# PSU.net
KiCad netlist of a schematic drawn in Altium Designer
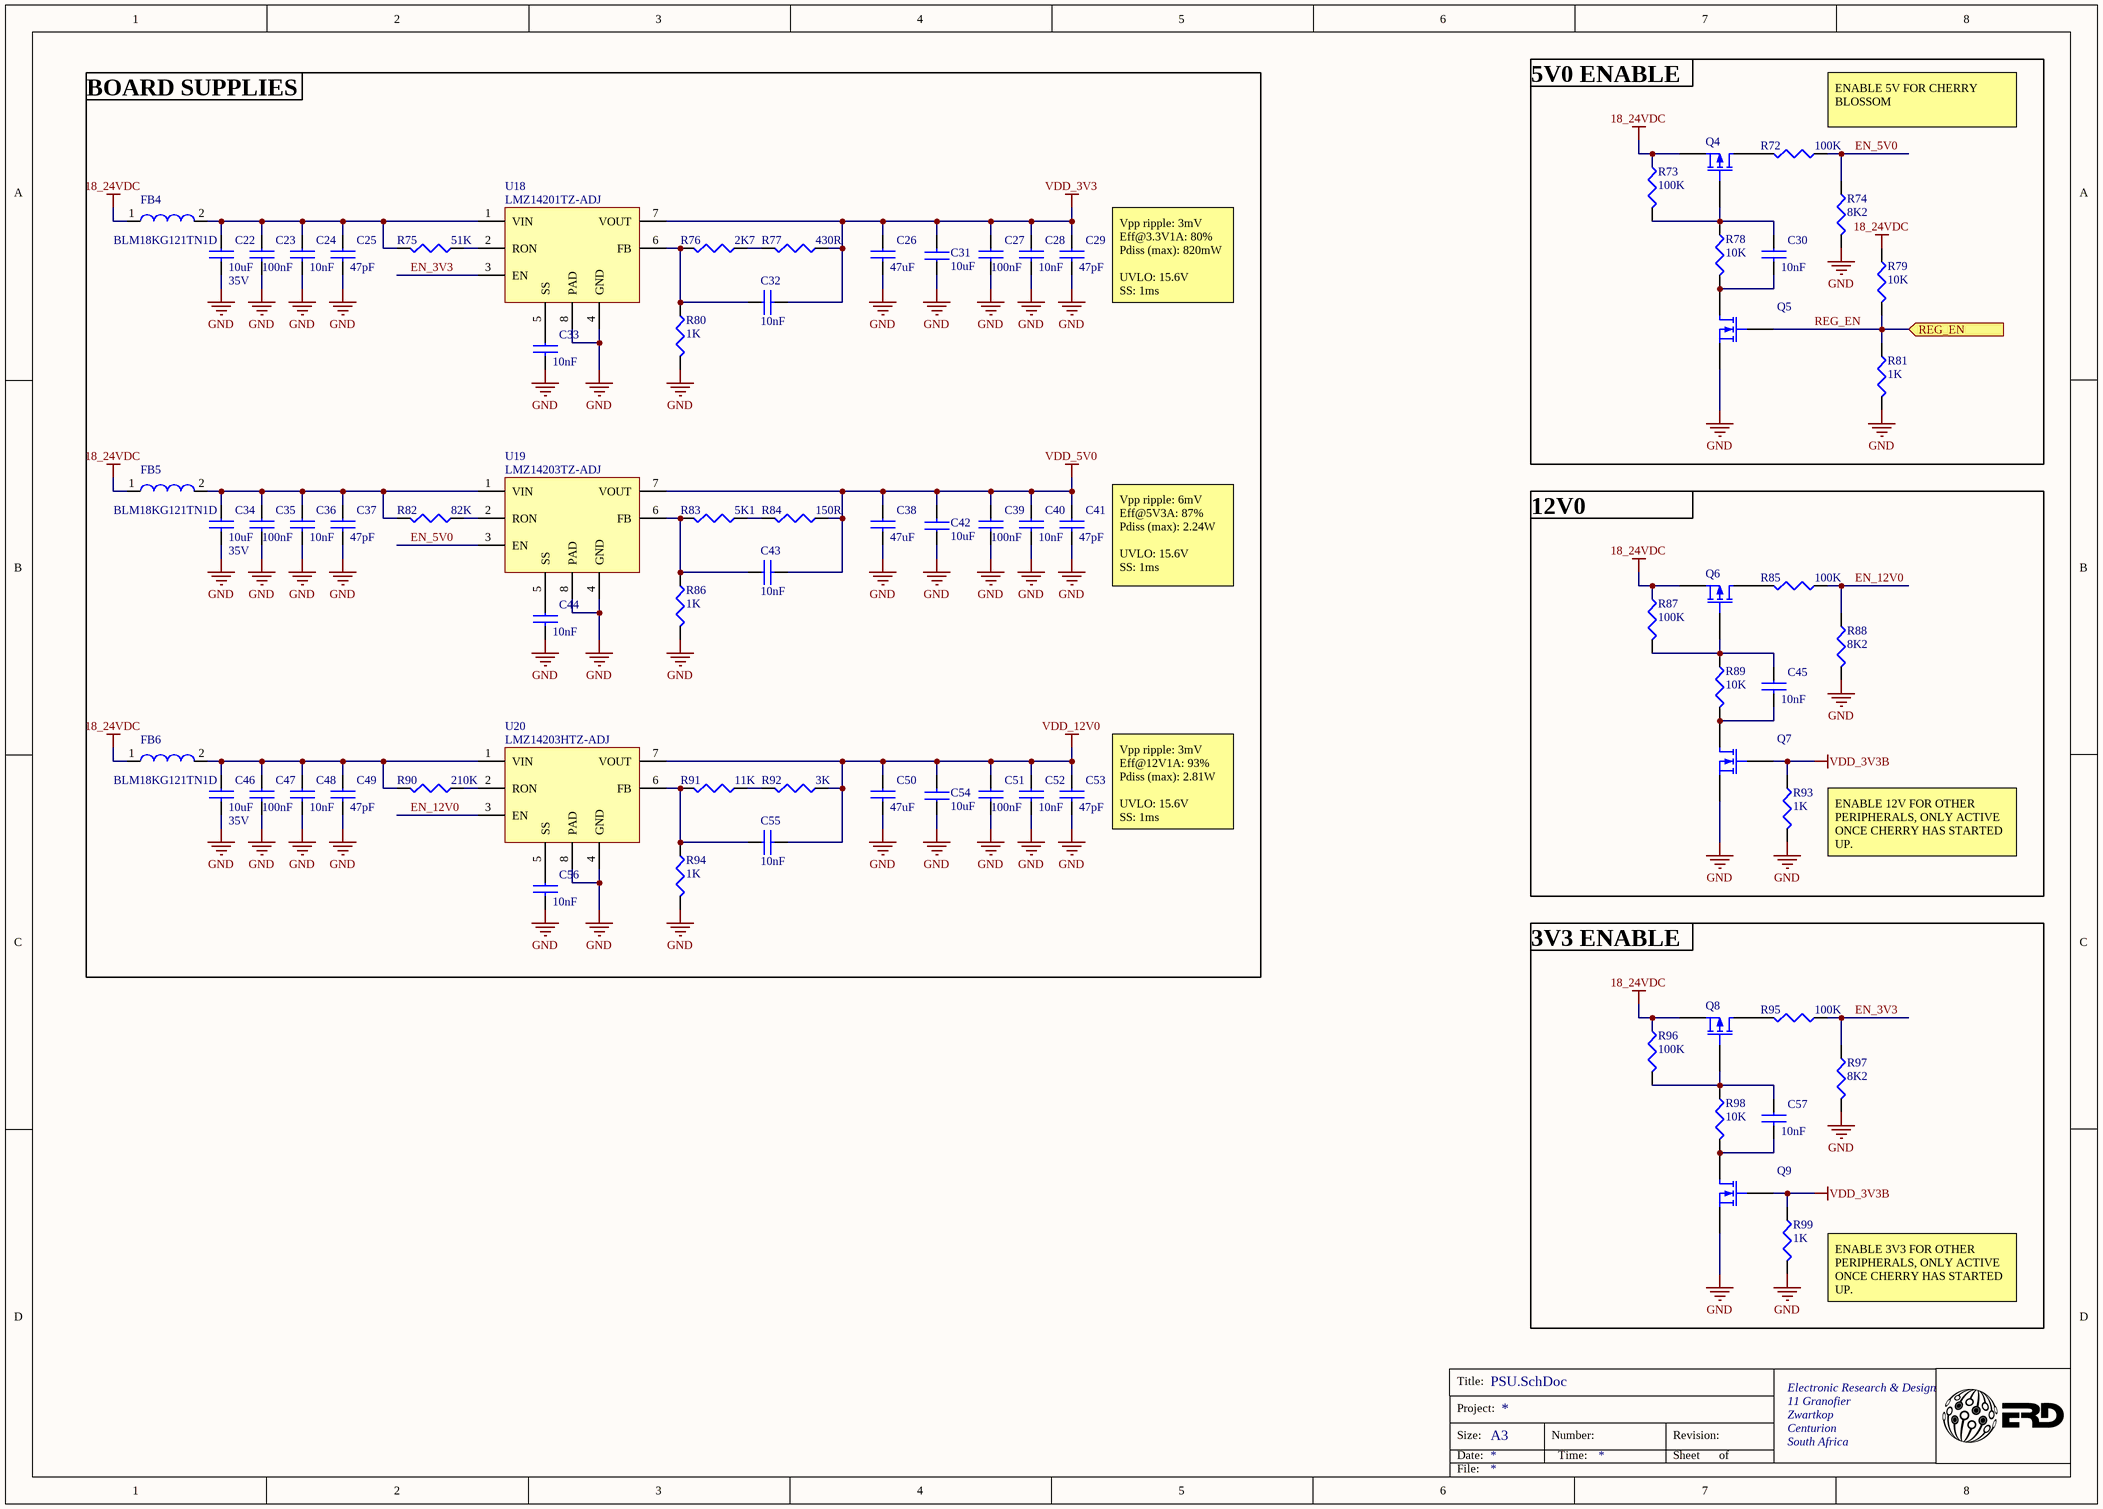
[diagram p0: PSU.SchDoc]

(export (version "E")
  (design (tool "Eeschema 10.0.6"))
  (components
    (comp (ref "C22")
      (value "10uF")
      (footprint "CC0805")
      (description "CAP CER 10UF 35V 10% X5R 0805")
      (fields
        (field (name "MANUFACTURER") "Murata")
        (field (name "PART NUMBER") "GRM21BR6YA106KE43L")
        (field (name "VOLTAGE RATING") "35V")
      )
      (libsource (lib "ERD TiAm") (part "CAP CER 0.1UF 10V 10% X5R 0402"))
    )
    (comp (ref "C23")
      (value "100nF")
      (footprint "CC0402")
      (description "CAP CER 0.1UF 50V 10% X7R 0402")
      (fields (field (name "MANUFACTURER") "Murata") (field (name "PART NUMBER") "GCM155R71H104KE02D"))
      (libsource (lib "ERD TiAm") (part "CAP CER 0.1UF 10V 10% X5R 0402"))
    )
    (comp (ref "C24")
      (value "10nF")
      (footprint "CC0402")
      (description "CAP CER 10NF 50V 10% X7R 0402")
      (fields (field (name "MANUFACTURER") "Murata") (field (name "PART NUMBER") "GRM155R71H103KA88J"))
      (libsource (lib "ERD TiAm") (part "CAP CER 0.1UF 10V 10% X5R 0402"))
    )
    (comp (ref "C25")
      (value "47pF")
      (footprint "CC0402")
      (description "CAP CER 47PF 50V 5% C0G/NP0 0402")
      (fields (field (name "MANUFACTURER") "Murata") (field (name "PART NUMBER") "GCM1555C1H470JA16D"))
      (libsource (lib "ERD TiAm") (part "CAP CER 0.1UF 10V 10% X5R 0402"))
    )
    (comp (ref "C26")
      (value "47uF")
      (footprint "RC1206")
      (description "CAP CER 47UF 25V 20% X5R 1206")
      (fields (field (name "MANUFACTURER") "Murata") (field (name "PART NUMBER") "C3216X5R1E476M160AC"))
      (libsource (lib "ERD TiAm") (part "CAP CER 0.1UF 10V 10% X5R 0402"))
    )
    (comp (ref "C27")
      (value "100nF")
      (footprint "CC0402")
      (description "CAP CER 0.1UF 50V 10% X7R 0402")
      (fields (field (name "MANUFACTURER") "Murata") (field (name "PART NUMBER") "GCM155R71H104KE02D"))
      (libsource (lib "ERD TiAm") (part "CAP CER 0.1UF 10V 10% X5R 0402"))
    )
    (comp (ref "C28")
      (value "10nF")
      (footprint "CC0402")
      (description "CAP CER 10NF 50V 10% X7R 0402")
      (fields (field (name "MANUFACTURER") "Murata") (field (name "PART NUMBER") "GRM155R71H103KA88J"))
      (libsource (lib "ERD TiAm") (part "CAP CER 0.1UF 10V 10% X5R 0402"))
    )
    (comp (ref "C29")
      (value "47pF")
      (footprint "CC0402")
      (description "CAP CER 47PF 50V 5% C0G/NP0 0402")
      (fields (field (name "MANUFACTURER") "Murata") (field (name "PART NUMBER") "GCM1555C1H470JA16D"))
      (libsource (lib "ERD TiAm") (part "CAP CER 0.1UF 10V 10% X5R 0402"))
    )
    (comp (ref "C30")
      (value "10nF")
      (footprint "CC0402")
      (description "CAP CER 10NF 50V 10% X7R 0402")
      (fields (field (name "MANUFACTURER") "Murata") (field (name "PART NUMBER") "GRM155R71H103KA88J"))
      (libsource (lib "ERD TiAm") (part "CAP CER 0.1UF 10V 10% X5R 0402"))
    )
    (comp (ref "C31")
      (value "10uF")
      (footprint "CC0603")
      (description "CAP CER 10UF 25V 20% X5R 0603")
      (fields (field (name "MANUFACTURER") "Murata") (field (name "PARTNUMBER") "GRM188R61E106MA73D"))
      (libsource (lib "ERD TiAm") (part "CAP CER 0.1UF 10V 10% X5R 0402"))
    )
    (comp (ref "C32")
      (value "10nF")
      (footprint "CC0402")
      (description "CAP CER 10NF 50V 10% X7R 0402")
      (fields (field (name "MANUFACTURER") "Murata") (field (name "PART NUMBER") "GRM155R71H103KA88J"))
      (libsource (lib "ERD TiAm") (part "CAP CER 0.1UF 10V 10% X5R 0402"))
    )
    (comp (ref "C33")
      (value "10nF")
      (footprint "CC0402")
      (description "CAP CER 10NF 50V 10% X7R 0402")
      (fields (field (name "MANUFACTURER") "Murata") (field (name "PART NUMBER") "GRM155R71H103KA88J"))
      (libsource (lib "ERD TiAm") (part "CAP CER 0.1UF 10V 10% X5R 0402"))
    )
    (comp (ref "C34")
      (value "10uF")
      (footprint "CC0805")
      (description "CAP CER 10UF 35V 10% X5R 0805")
      (fields
        (field (name "MANUFACTURER") "Murata")
        (field (name "PART NUMBER") "GRM21BR6YA106KE43L")
        (field (name "VOLTAGE RATING") "35V")
      )
      (libsource (lib "ERD TiAm") (part "CAP CER 0.1UF 10V 10% X5R 0402"))
    )
    (comp (ref "C35")
      (value "100nF")
      (footprint "CC0402")
      (description "CAP CER 0.1UF 50V 10% X7R 0402")
      (fields (field (name "MANUFACTURER") "Murata") (field (name "PART NUMBER") "GCM155R71H104KE02D"))
      (libsource (lib "ERD TiAm") (part "CAP CER 0.1UF 10V 10% X5R 0402"))
    )
    (comp (ref "C36")
      (value "10nF")
      (footprint "CC0402")
      (description "CAP CER 10NF 50V 10% X7R 0402")
      (fields (field (name "MANUFACTURER") "Murata") (field (name "PART NUMBER") "GRM155R71H103KA88J"))
      (libsource (lib "ERD TiAm") (part "CAP CER 0.1UF 10V 10% X5R 0402"))
    )
    (comp (ref "C37")
      (value "47pF")
      (footprint "CC0402")
      (description "CAP CER 47PF 50V 5% C0G/NP0 0402")
      (fields (field (name "MANUFACTURER") "Murata") (field (name "PART NUMBER") "GCM1555C1H470JA16D"))
      (libsource (lib "ERD TiAm") (part "CAP CER 0.1UF 10V 10% X5R 0402"))
    )
    (comp (ref "C38")
      (value "47uF")
      (footprint "RC1206")
      (description "CAP CER 47UF 25V 20% X5R 1206")
      (fields (field (name "MANUFACTURER") "Murata") (field (name "PART NUMBER") "C3216X5R1E476M160AC"))
      (libsource (lib "ERD TiAm") (part "CAP CER 0.1UF 10V 10% X5R 0402"))
    )
    (comp (ref "C39")
      (value "100nF")
      (footprint "CC0402")
      (description "CAP CER 0.1UF 50V 10% X7R 0402")
      (fields (field (name "MANUFACTURER") "Murata") (field (name "PART NUMBER") "GCM155R71H104KE02D"))
      (libsource (lib "ERD TiAm") (part "CAP CER 0.1UF 10V 10% X5R 0402"))
    )
    (comp (ref "C40")
      (value "10nF")
      (footprint "CC0402")
      (description "CAP CER 10NF 50V 10% X7R 0402")
      (fields (field (name "MANUFACTURER") "Murata") (field (name "PART NUMBER") "GRM155R71H103KA88J"))
      (libsource (lib "ERD TiAm") (part "CAP CER 0.1UF 10V 10% X5R 0402"))
    )
    (comp (ref "C41")
      (value "47pF")
      (footprint "CC0402")
      (description "CAP CER 47PF 50V 5% C0G/NP0 0402")
      (fields (field (name "MANUFACTURER") "Murata") (field (name "PART NUMBER") "GCM1555C1H470JA16D"))
      (libsource (lib "ERD TiAm") (part "CAP CER 0.1UF 10V 10% X5R 0402"))
    )
    (comp (ref "C42")
      (value "10uF")
      (footprint "CC0603")
      (description "CAP CER 10UF 25V 20% X5R 0603")
      (fields (field (name "MANUFACTURER") "Murata") (field (name "PARTNUMBER") "GRM188R61E106MA73D"))
      (libsource (lib "ERD TiAm") (part "CAP CER 0.1UF 10V 10% X5R 0402"))
    )
    (comp (ref "C43")
      (value "10nF")
      (footprint "CC0402")
      (description "CAP CER 10NF 50V 10% X7R 0402")
      (fields (field (name "MANUFACTURER") "Murata") (field (name "PART NUMBER") "GRM155R71H103KA88J"))
      (libsource (lib "ERD TiAm") (part "CAP CER 0.1UF 10V 10% X5R 0402"))
    )
    (comp (ref "C44")
      (value "10nF")
      (footprint "CC0402")
      (description "CAP CER 10NF 50V 10% X7R 0402")
      (fields (field (name "MANUFACTURER") "Murata") (field (name "PART NUMBER") "GRM155R71H103KA88J"))
      (libsource (lib "ERD TiAm") (part "CAP CER 0.1UF 10V 10% X5R 0402"))
    )
    (comp (ref "C45")
      (value "10nF")
      (footprint "CC0402")
      (description "CAP CER 10NF 50V 10% X7R 0402")
      (fields (field (name "MANUFACTURER") "Murata") (field (name "PART NUMBER") "GRM155R71H103KA88J"))
      (libsource (lib "ERD TiAm") (part "CAP CER 0.1UF 10V 10% X5R 0402"))
    )
    (comp (ref "C46")
      (value "10uF")
      (footprint "CC0805")
      (description "CAP CER 10UF 35V 10% X5R 0805")
      (fields
        (field (name "MANUFACTURER") "Murata")
        (field (name "PART NUMBER") "GRM21BR6YA106KE43L")
        (field (name "VOLTAGE RATING") "35V")
      )
      (libsource (lib "ERD TiAm") (part "CAP CER 0.1UF 10V 10% X5R 0402"))
    )
    (comp (ref "C47")
      (value "100nF")
      (footprint "CC0402")
      (description "CAP CER 0.1UF 50V 10% X7R 0402")
      (fields (field (name "MANUFACTURER") "Murata") (field (name "PART NUMBER") "GCM155R71H104KE02D"))
      (libsource (lib "ERD TiAm") (part "CAP CER 0.1UF 10V 10% X5R 0402"))
    )
    (comp (ref "C48")
      (value "10nF")
      (footprint "CC0402")
      (description "CAP CER 10NF 50V 10% X7R 0402")
      (fields (field (name "MANUFACTURER") "Murata") (field (name "PART NUMBER") "GRM155R71H103KA88J"))
      (libsource (lib "ERD TiAm") (part "CAP CER 0.1UF 10V 10% X5R 0402"))
    )
    (comp (ref "C49")
      (value "47pF")
      (footprint "CC0402")
      (description "CAP CER 47PF 50V 5% C0G/NP0 0402")
      (fields (field (name "MANUFACTURER") "Murata") (field (name "PART NUMBER") "GCM1555C1H470JA16D"))
      (libsource (lib "ERD TiAm") (part "CAP CER 0.1UF 10V 10% X5R 0402"))
    )
    (comp (ref "C50")
      (value "47uF")
      (footprint "RC1206")
      (description "CAP CER 47UF 25V 20% X5R 1206")
      (fields (field (name "MANUFACTURER") "Murata") (field (name "PART NUMBER") "C3216X5R1E476M160AC"))
      (libsource (lib "ERD TiAm") (part "CAP CER 0.1UF 10V 10% X5R 0402"))
    )
    (comp (ref "C51")
      (value "100nF")
      (footprint "CC0402")
      (description "CAP CER 0.1UF 50V 10% X7R 0402")
      (fields (field (name "MANUFACTURER") "Murata") (field (name "PART NUMBER") "GCM155R71H104KE02D"))
      (libsource (lib "ERD TiAm") (part "CAP CER 0.1UF 10V 10% X5R 0402"))
    )
    (comp (ref "C52")
      (value "10nF")
      (footprint "CC0402")
      (description "CAP CER 10NF 50V 10% X7R 0402")
      (fields (field (name "MANUFACTURER") "Murata") (field (name "PART NUMBER") "GRM155R71H103KA88J"))
      (libsource (lib "ERD TiAm") (part "CAP CER 0.1UF 10V 10% X5R 0402"))
    )
    (comp (ref "C53")
      (value "47pF")
      (footprint "CC0402")
      (description "CAP CER 47PF 50V 5% C0G/NP0 0402")
      (fields (field (name "MANUFACTURER") "Murata") (field (name "PART NUMBER") "GCM1555C1H470JA16D"))
      (libsource (lib "ERD TiAm") (part "CAP CER 0.1UF 10V 10% X5R 0402"))
    )
    (comp (ref "C54")
      (value "10uF")
      (footprint "CC0603")
      (description "CAP CER 10UF 25V 20% X5R 0603")
      (fields (field (name "MANUFACTURER") "Murata") (field (name "PARTNUMBER") "GRM188R61E106MA73D"))
      (libsource (lib "ERD TiAm") (part "CAP CER 0.1UF 10V 10% X5R 0402"))
    )
    (comp (ref "C55")
      (value "10nF")
      (footprint "CC0402")
      (description "CAP CER 10NF 50V 10% X7R 0402")
      (fields (field (name "MANUFACTURER") "Murata") (field (name "PART NUMBER") "GRM155R71H103KA88J"))
      (libsource (lib "ERD TiAm") (part "CAP CER 0.1UF 10V 10% X5R 0402"))
    )
    (comp (ref "C56")
      (value "10nF")
      (footprint "CC0402")
      (description "CAP CER 10NF 50V 10% X7R 0402")
      (fields (field (name "MANUFACTURER") "Murata") (field (name "PART NUMBER") "GRM155R71H103KA88J"))
      (libsource (lib "ERD TiAm") (part "CAP CER 0.1UF 10V 10% X5R 0402"))
    )
    (comp (ref "C57")
      (value "10nF")
      (footprint "CC0402")
      (description "CAP CER 10NF 50V 10% X7R 0402")
      (fields (field (name "MANUFACTURER") "Murata") (field (name "PART NUMBER") "GRM155R71H103KA88J"))
      (libsource (lib "ERD TiAm") (part "CAP CER 0.1UF 10V 10% X5R 0402"))
    )
    (comp (ref "FB4")
      (value "BLM18KG121TN1D")
      (footprint "LC0603")
      (description "FERRITE 3A 30mOHM 0603 SMD")
      (libsource (lib "BEAGLEBONEBLACK_REV A5B") (part "FER_180_200_0"))
    )
    (comp (ref "FB5")
      (value "BLM18KG121TN1D")
      (footprint "LC0603")
      (description "FERRITE 3A 30mOHM 0603 SMD")
      (libsource (lib "BEAGLEBONEBLACK_REV A5B") (part "FER_180_200_0"))
    )
    (comp (ref "FB6")
      (value "BLM18KG121TN1D")
      (footprint "LC0603")
      (description "FERRITE 3A 30mOHM 0603 SMD")
      (libsource (lib "BEAGLEBONEBLACK_REV A5B") (part "FER_180_200_0"))
    )
    (comp (ref "Q4")
      (value "MOSFET-P")
      (footprint "E3")
      (description "P-Channel MOSFET")
      (fields (field (name "PUBLISHER") "Altium Limited"))
      (libsource (lib "Miscellaneous Devices") (part "MOSFET-P"))
    )
    (comp (ref "Q5")
      (value "BSS214NWH6327XTSA1")
      (footprint "ERD TiAm:SOT323")
      (description "N-Channel FET, 20V, 1.5A, 140mOhm, SOT323")
      (fields (field (name "PUBLISHER") "Altium Limited"))
      (libsource (lib "Miscellaneous Devices") (part "MOSFET-N"))
    )
    (comp (ref "Q6")
      (value "MOSFET-P")
      (footprint "E3")
      (description "P-Channel MOSFET")
      (fields (field (name "PUBLISHER") "Altium Limited"))
      (libsource (lib "Miscellaneous Devices") (part "MOSFET-P"))
    )
    (comp (ref "Q7")
      (value "BSS214NWH6327XTSA1")
      (footprint "ERD TiAm:SOT323")
      (description "N-Channel FET, 20V, 1.5A, 140mOhm, SOT323")
      (fields (field (name "PUBLISHER") "Altium Limited"))
      (libsource (lib "Miscellaneous Devices") (part "MOSFET-N"))
    )
    (comp (ref "Q8")
      (value "MOSFET-P")
      (footprint "E3")
      (description "P-Channel MOSFET")
      (fields (field (name "PUBLISHER") "Altium Limited"))
      (libsource (lib "Miscellaneous Devices") (part "MOSFET-P"))
    )
    (comp (ref "Q9")
      (value "BSS214NWH6327XTSA1")
      (footprint "ERD TiAm:SOT323")
      (description "N-Channel FET, 20V, 1.5A, 140mOhm, SOT323")
      (fields (field (name "PUBLISHER") "Altium Limited"))
      (libsource (lib "Miscellaneous Devices") (part "MOSFET-N"))
    )
    (comp (ref "R72")
      (value "100K")
      (footprint "RC0402")
      (description "RES, 100K OHM, 1/16W, 1%, 0402")
      (fields (field (name "MANUFACTURER") "Yageo") (field (name "PARTNUMBER") "RC0402FR-07100KL"))
      (libsource (lib "ERD TiAm") (part "RES_10K_1/16W_1%_0402"))
    )
    (comp (ref "R73")
      (value "100K")
      (footprint "RC0402")
      (description "RES, 100K OHM, 1/16W, 1%, 0402")
      (fields (field (name "MANUFACTURER") "Yageo") (field (name "PART NUMBER") "RC0402FR-07100KL"))
      (libsource (lib "ERD TiAm") (part "RES_10K_1/16W_1%_0402"))
    )
    (comp (ref "R74")
      (value "8K2")
      (footprint "RC0402")
      (description "RES, 8K2 OHM, 1/16W, 1%, 0402")
      (fields (field (name "MANUFACTURER") "Yageo") (field (name "PARTNUMBER") "RC0402FR-078K2L"))
      (libsource (lib "ERD TiAm") (part "RES_10K_1/16W_1%_0402"))
    )
    (comp (ref "R75")
      (value "51K")
      (footprint "RC0402")
      (description "RES, 51K OHM, 1/16W, 1%, 0402")
      (fields (field (name "MANUFACTURER") "Yageo") (field (name "PARTNUMBER") "RC0402FR-0751KL"))
      (libsource (lib "ERD TiAm") (part "RES_10K_1/16W_1%_0402"))
    )
    (comp (ref "R76")
      (value "2K7")
      (footprint "RC0402")
      (description "RES, 2K7 OHM, 1/16W, 1%, 0402")
      (fields (field (name "MANUFACTURER") "Yageo") (field (name "PARTNUMBER") "RC0402FR-072K7L"))
      (libsource (lib "ERD TiAm") (part "RES_10K_1/16W_1%_0402"))
    )
    (comp (ref "R77")
      (value "430R")
      (footprint "RC0402")
      (description "RES, 430 OHM, 1/16W, 1%, 0402")
      (fields (field (name "MANUFACTURER") "Yageo") (field (name "PARTNUMBER") "RC0402FR-07430RL"))
      (libsource (lib "ERD TiAm") (part "RES_10K_1/16W_1%_0402"))
    )
    (comp (ref "R78")
      (value "10K")
      (footprint "RC0402")
      (description "RES, 10K OHM, 1/16W, 1%, 0402")
      (fields (field (name "MANUFACTURER") "Yageo") (field (name "PART NUMBER") "RC0402FR-0710KL"))
      (libsource (lib "ERD TiAm") (part "RES_10K_1/16W_1%_0402"))
    )
    (comp (ref "R79")
      (value "10K")
      (footprint "RC0402")
      (description "RES, 10K OHM, 1/16W, 1%, 0402")
      (fields (field (name "MANUFACTURER") "Yageo") (field (name "PART NUMBER") "RC0402FR-0710KL"))
      (libsource (lib "ERD TiAm") (part "RES_10K_1/16W_1%_0402"))
    )
    (comp (ref "R80")
      (value "1K")
      (footprint "RC0402")
      (description "RES, 1K OHM, 1/16W, 1%, 0402")
      (fields (field (name "MANUFACTURER") "Yageo") (field (name "PARTNUMBER") "RC0402FR-071KL"))
      (libsource (lib "ERD TiAm") (part "RES_10K_1/16W_1%_0402"))
    )
    (comp (ref "R81")
      (value "1K")
      (footprint "RC0402")
      (description "RES, 1K OHM, 1/16W, 1%, 0402")
      (fields (field (name "MANUFACTURER") "Yageo") (field (name "PARTNUMBER") "RC0402FR-071KL"))
      (libsource (lib "ERD TiAm") (part "RES_10K_1/16W_1%_0402"))
    )
    (comp (ref "R82")
      (value "82K")
      (footprint "RC0402")
      (description "RES, 82K OHM, 1/16W, 1%, 0402")
      (fields (field (name "MANUFACTURER") "Yageo") (field (name "PARTNUMBER") "RC0402FR-0782KL"))
      (libsource (lib "ERD TiAm") (part "RES_10K_1/16W_1%_0402"))
    )
    (comp (ref "R83")
      (value "5K1")
      (footprint "RC0402")
      (description "RES, 5K1 OHM, 1/16W, 1%, 0402")
      (fields (field (name "MANUFACTURER") "Yageo") (field (name "PARTNUMBER") "RC0402FR-075K1L"))
      (libsource (lib "ERD TiAm") (part "RES_10K_1/16W_1%_0402"))
    )
    (comp (ref "R84")
      (value "150R")
      (footprint "RC0402")
      (description "RES, 150 OHM, 1/16W, 1%, 0402")
      (fields (field (name "MANUFACTURER") "Yageo") (field (name "PARTNUMBER") "RC0402FR-07150RL"))
      (libsource (lib "ERD TiAm") (part "RES_10K_1/16W_1%_0402"))
    )
    (comp (ref "R85")
      (value "100K")
      (footprint "RC0402")
      (description "RES, 100K OHM, 1/16W, 1%, 0402")
      (fields (field (name "MANUFACTURER") "Yageo") (field (name "PARTNUMBER") "RC0402FR-07100KL"))
      (libsource (lib "ERD TiAm") (part "RES_10K_1/16W_1%_0402"))
    )
    (comp (ref "R86")
      (value "1K")
      (footprint "RC0402")
      (description "RES, 1K OHM, 1/16W, 1%, 0402")
      (fields (field (name "MANUFACTURER") "Yageo") (field (name "PARTNUMBER") "RC0402FR-071KL"))
      (libsource (lib "ERD TiAm") (part "RES_10K_1/16W_1%_0402"))
    )
    (comp (ref "R87")
      (value "100K")
      (footprint "RC0402")
      (description "RES, 100K OHM, 1/16W, 1%, 0402")
      (fields (field (name "MANUFACTURER") "Yageo") (field (name "PART NUMBER") "RC0402FR-07100KL"))
      (libsource (lib "ERD TiAm") (part "RES_10K_1/16W_1%_0402"))
    )
    (comp (ref "R88")
      (value "8K2")
      (footprint "RC0402")
      (description "RES, 8K2 OHM, 1/16W, 1%, 0402")
      (fields (field (name "MANUFACTURER") "Yageo") (field (name "PARTNUMBER") "RC0402FR-078K2L"))
      (libsource (lib "ERD TiAm") (part "RES_10K_1/16W_1%_0402"))
    )
    (comp (ref "R89")
      (value "10K")
      (footprint "RC0402")
      (description "RES, 10K OHM, 1/16W, 1%, 0402")
      (fields (field (name "MANUFACTURER") "Yageo") (field (name "PART NUMBER") "RC0402FR-0710KL"))
      (libsource (lib "ERD TiAm") (part "RES_10K_1/16W_1%_0402"))
    )
    (comp (ref "R90")
      (value "210K")
      (footprint "RC0402")
      (description "RES, 210K OHM, 1/16W, 1%, 0402")
      (fields (field (name "MANUFACTURER") "Yageo") (field (name "PARTNUMBER") "RC0402FR-07210KL"))
      (libsource (lib "ERD TiAm") (part "RES_10K_1/16W_1%_0402"))
    )
    (comp (ref "R91")
      (value "11K")
      (footprint "RC0402")
      (description "RES, 11K OHM, 1/16W, 1%, 0402")
      (fields (field (name "MANUFACTURER") "Yageo") (field (name "PARTNUMBER") "RC0402FR-0711KL"))
      (libsource (lib "ERD TiAm") (part "RES_10K_1/16W_1%_0402"))
    )
    (comp (ref "R92")
      (value "3K")
      (footprint "RC0402")
      (description "RES, 3K OHM, 1/16W, 1%, 0402")
      (fields (field (name "MANUFACTURER") "Yageo") (field (name "PARTNUMBER") "RC0402FR-073KL"))
      (libsource (lib "ERD TiAm") (part "RES_10K_1/16W_1%_0402"))
    )
    (comp (ref "R93")
      (value "1K")
      (footprint "RC0402")
      (description "RES, 1K OHM, 1/16W, 1%, 0402")
      (fields (field (name "MANUFACTURER") "Yageo") (field (name "PARTNUMBER") "RC0402FR-071KL"))
      (libsource (lib "ERD TiAm") (part "RES_10K_1/16W_1%_0402"))
    )
    (comp (ref "R94")
      (value "1K")
      (footprint "RC0402")
      (description "RES, 1K OHM, 1/16W, 1%, 0402")
      (fields (field (name "MANUFACTURER") "Yageo") (field (name "PARTNUMBER") "RC0402FR-071KL"))
      (libsource (lib "ERD TiAm") (part "RES_10K_1/16W_1%_0402"))
    )
    (comp (ref "R95")
      (value "100K")
      (footprint "RC0402")
      (description "RES, 100K OHM, 1/16W, 1%, 0402")
      (fields (field (name "MANUFACTURER") "Yageo") (field (name "PARTNUMBER") "RC0402FR-07100KL"))
      (libsource (lib "ERD TiAm") (part "RES_10K_1/16W_1%_0402"))
    )
    (comp (ref "R96")
      (value "100K")
      (footprint "RC0402")
      (description "RES, 100K OHM, 1/16W, 1%, 0402")
      (fields (field (name "MANUFACTURER") "Yageo") (field (name "PART NUMBER") "RC0402FR-07100KL"))
      (libsource (lib "ERD TiAm") (part "RES_10K_1/16W_1%_0402"))
    )
    (comp (ref "R97")
      (value "8K2")
      (footprint "RC0402")
      (description "RES, 8K2 OHM, 1/16W, 1%, 0402")
      (fields (field (name "MANUFACTURER") "Yageo") (field (name "PARTNUMBER") "RC0402FR-078K2L"))
      (libsource (lib "ERD TiAm") (part "RES_10K_1/16W_1%_0402"))
    )
    (comp (ref "R98")
      (value "10K")
      (footprint "RC0402")
      (description "RES, 10K OHM, 1/16W, 1%, 0402")
      (fields (field (name "MANUFACTURER") "Yageo") (field (name "PART NUMBER") "RC0402FR-0710KL"))
      (libsource (lib "ERD TiAm") (part "RES_10K_1/16W_1%_0402"))
    )
    (comp (ref "R99")
      (value "1K")
      (footprint "RC0402")
      (description "RES, 1K OHM, 1/16W, 1%, 0402")
      (fields (field (name "MANUFACTURER") "Yageo") (field (name "PARTNUMBER") "RC0402FR-071KL"))
      (libsource (lib "ERD TiAm") (part "RES_10K_1/16W_1%_0402"))
    )
    (comp (ref "U18")
      (value "LMZ14201TZ-ADJ")
      (footprint "TZA07A")
      (description "Buc Converter, SimpleSwitcher, 42V, 1A, TO-PMOD-7")
      (fields (field (name "MANUFACTURER") "Texas Instruments"))
      (libsource (lib "ERD TiAm") (part "LMZ14201"))
    )
    (comp (ref "U19")
      (value "LMZ14203TZ-ADJ")
      (footprint "TZA07A")
      (description "Buc Converter, SimpleSwitcher, 42V, 1A, TO-PMOD-7")
      (fields (field (name "MANUFACTURER") "Texas Instruments"))
      (libsource (lib "ERD TiAm") (part "LMZ14201"))
    )
    (comp (ref "U20")
      (value "LMZ14203HTZ-ADJ")
      (footprint "TZA07A")
      (description "Buc Converter, SimpleSwitcher, 42V, 1A, TO-PMOD-7")
      (fields (field (name "MANUFACTURER") "Texas Instruments"))
      (libsource (lib "ERD TiAm") (part "LMZ14201"))
    )
  )
  (nets
    (net (code "1") (name "/EN_3V3") (class "Default")
      (node (ref "R95") (pin "1") (pinfunction "1_1") (pintype "passive"))
      (node (ref "R97") (pin "1") (pinfunction "1_1") (pintype "passive"))
      (node (ref "U18") (pin "3") (pinfunction "EN_3") (pintype "power_in"))
    )
    (net (code "2") (name "/EN_5V0") (class "Default")
      (node (ref "R72") (pin "1") (pinfunction "1_1") (pintype "passive"))
      (node (ref "R74") (pin "1") (pinfunction "1_1") (pintype "passive"))
      (node (ref "U19") (pin "3") (pinfunction "EN_3") (pintype "power_in"))
    )
    (net (code "3") (name "/EN_12V0") (class "Default")
      (node (ref "R85") (pin "1") (pinfunction "1_1") (pintype "passive"))
      (node (ref "R88") (pin "1") (pinfunction "1_1") (pintype "passive"))
      (node (ref "U20") (pin "3") (pinfunction "EN_3") (pintype "power_in"))
    )
    (net (code "4") (name "/REG_EN") (class "Default")
      (node (ref "Q5") (pin "2") (pinfunction "G_2") (pintype "passive"))
      (node (ref "R79") (pin "2") (pinfunction "2_2") (pintype "passive"))
      (node (ref "R81") (pin "1") (pinfunction "1_1") (pintype "passive"))
    )
    (net (code "5") (name "18_24VDC") (class "Default")
      (node (ref "FB4") (pin "1") (pinfunction "1_1") (pintype "passive"))
      (node (ref "FB5") (pin "1") (pinfunction "1_1") (pintype "passive"))
      (node (ref "FB6") (pin "1") (pinfunction "1_1") (pintype "passive"))
      (node (ref "Q4") (pin "3") (pinfunction "S_3") (pintype "passive"))
      (node (ref "Q6") (pin "3") (pinfunction "S_3") (pintype "passive"))
      (node (ref "Q8") (pin "3") (pinfunction "S_3") (pintype "passive"))
      (node (ref "R73") (pin "1") (pinfunction "1_1") (pintype "passive"))
      (node (ref "R79") (pin "1") (pinfunction "1_1") (pintype "passive"))
      (node (ref "R87") (pin "1") (pinfunction "1_1") (pintype "passive"))
      (node (ref "R96") (pin "1") (pinfunction "1_1") (pintype "passive"))
    )
    (net (code "6") (name "GND") (class "Default")
      (node (ref "C22") (pin "2") (pinfunction "2_2") (pintype "passive"))
      (node (ref "C23") (pin "2") (pinfunction "2_2") (pintype "passive"))
      (node (ref "C24") (pin "2") (pinfunction "2_2") (pintype "passive"))
      (node (ref "C25") (pin "2") (pinfunction "2_2") (pintype "passive"))
      (node (ref "C26") (pin "2") (pinfunction "2_2") (pintype "passive"))
      (node (ref "C27") (pin "2") (pinfunction "2_2") (pintype "passive"))
      (node (ref "C28") (pin "2") (pinfunction "2_2") (pintype "passive"))
      (node (ref "C29") (pin "2") (pinfunction "2_2") (pintype "passive"))
      (node (ref "C31") (pin "1") (pinfunction "1_1") (pintype "passive"))
      (node (ref "C33") (pin "2") (pinfunction "2_2") (pintype "passive"))
      (node (ref "C34") (pin "2") (pinfunction "2_2") (pintype "passive"))
      (node (ref "C35") (pin "2") (pinfunction "2_2") (pintype "passive"))
      (node (ref "C36") (pin "2") (pinfunction "2_2") (pintype "passive"))
      (node (ref "C37") (pin "2") (pinfunction "2_2") (pintype "passive"))
      (node (ref "C38") (pin "2") (pinfunction "2_2") (pintype "passive"))
      (node (ref "C39") (pin "2") (pinfunction "2_2") (pintype "passive"))
      (node (ref "C40") (pin "2") (pinfunction "2_2") (pintype "passive"))
      (node (ref "C41") (pin "2") (pinfunction "2_2") (pintype "passive"))
      (node (ref "C42") (pin "1") (pinfunction "1_1") (pintype "passive"))
      (node (ref "C44") (pin "2") (pinfunction "2_2") (pintype "passive"))
      (node (ref "C46") (pin "2") (pinfunction "2_2") (pintype "passive"))
      (node (ref "C47") (pin "2") (pinfunction "2_2") (pintype "passive"))
      (node (ref "C48") (pin "2") (pinfunction "2_2") (pintype "passive"))
      (node (ref "C49") (pin "2") (pinfunction "2_2") (pintype "passive"))
      (node (ref "C50") (pin "2") (pinfunction "2_2") (pintype "passive"))
      (node (ref "C51") (pin "2") (pinfunction "2_2") (pintype "passive"))
      (node (ref "C52") (pin "2") (pinfunction "2_2") (pintype "passive"))
      (node (ref "C53") (pin "2") (pinfunction "2_2") (pintype "passive"))
      (node (ref "C54") (pin "1") (pinfunction "1_1") (pintype "passive"))
      (node (ref "C56") (pin "2") (pinfunction "2_2") (pintype "passive"))
      (node (ref "Q5") (pin "3") (pinfunction "S_3") (pintype "passive"))
      (node (ref "Q7") (pin "3") (pinfunction "S_3") (pintype "passive"))
      (node (ref "Q9") (pin "3") (pinfunction "S_3") (pintype "passive"))
      (node (ref "R74") (pin "2") (pinfunction "2_2") (pintype "passive"))
      (node (ref "R80") (pin "2") (pinfunction "2_2") (pintype "passive"))
      (node (ref "R81") (pin "2") (pinfunction "2_2") (pintype "passive"))
      (node (ref "R86") (pin "2") (pinfunction "2_2") (pintype "passive"))
      (node (ref "R88") (pin "2") (pinfunction "2_2") (pintype "passive"))
      (node (ref "R93") (pin "2") (pinfunction "2_2") (pintype "passive"))
      (node (ref "R94") (pin "2") (pinfunction "2_2") (pintype "passive"))
      (node (ref "R97") (pin "2") (pinfunction "2_2") (pintype "passive"))
      (node (ref "R99") (pin "2") (pinfunction "2_2") (pintype "passive"))
      (node (ref "U18") (pin "4") (pinfunction "GND_4") (pintype "power_in"))
      (node (ref "U18") (pin "8") (pinfunction "PAD_8") (pintype "power_in"))
      (node (ref "U19") (pin "4") (pinfunction "GND_4") (pintype "power_in"))
      (node (ref "U19") (pin "8") (pinfunction "PAD_8") (pintype "power_in"))
      (node (ref "U20") (pin "4") (pinfunction "GND_4") (pintype "power_in"))
      (node (ref "U20") (pin "8") (pinfunction "PAD_8") (pintype "power_in"))
    )
    (net (code "7") (name "Net-(Q4-D)") (class "Default")
      (node (ref "Q4") (pin "1") (pinfunction "D_1") (pintype "passive"))
      (node (ref "R72") (pin "2") (pinfunction "2_2") (pintype "passive"))
    )
    (net (code "8") (name "Net-(Q4-G)") (class "Default")
      (node (ref "C30") (pin "1") (pinfunction "1_1") (pintype "passive"))
      (node (ref "Q4") (pin "2") (pinfunction "G_2") (pintype "passive"))
      (node (ref "R73") (pin "2") (pinfunction "2_2") (pintype "passive"))
      (node (ref "R78") (pin "1") (pinfunction "1_1") (pintype "passive"))
    )
    (net (code "9") (name "Net-(Q5-D)") (class "Default")
      (node (ref "C30") (pin "2") (pinfunction "2_2") (pintype "passive"))
      (node (ref "Q5") (pin "1") (pinfunction "D_1") (pintype "passive"))
      (node (ref "R78") (pin "2") (pinfunction "2_2") (pintype "passive"))
    )
    (net (code "10") (name "Net-(Q6-D)") (class "Default")
      (node (ref "Q6") (pin "1") (pinfunction "D_1") (pintype "passive"))
      (node (ref "R85") (pin "2") (pinfunction "2_2") (pintype "passive"))
    )
    (net (code "11") (name "Net-(Q6-G)") (class "Default")
      (node (ref "C45") (pin "1") (pinfunction "1_1") (pintype "passive"))
      (node (ref "Q6") (pin "2") (pinfunction "G_2") (pintype "passive"))
      (node (ref "R87") (pin "2") (pinfunction "2_2") (pintype "passive"))
      (node (ref "R89") (pin "1") (pinfunction "1_1") (pintype "passive"))
    )
    (net (code "12") (name "Net-(Q7-D)") (class "Default")
      (node (ref "C45") (pin "2") (pinfunction "2_2") (pintype "passive"))
      (node (ref "Q7") (pin "1") (pinfunction "D_1") (pintype "passive"))
      (node (ref "R89") (pin "2") (pinfunction "2_2") (pintype "passive"))
    )
    (net (code "13") (name "Net-(Q8-D)") (class "Default")
      (node (ref "Q8") (pin "1") (pinfunction "D_1") (pintype "passive"))
      (node (ref "R95") (pin "2") (pinfunction "2_2") (pintype "passive"))
    )
    (net (code "14") (name "Net-(Q8-G)") (class "Default")
      (node (ref "C57") (pin "1") (pinfunction "1_1") (pintype "passive"))
      (node (ref "Q8") (pin "2") (pinfunction "G_2") (pintype "passive"))
      (node (ref "R96") (pin "2") (pinfunction "2_2") (pintype "passive"))
      (node (ref "R98") (pin "1") (pinfunction "1_1") (pintype "passive"))
    )
    (net (code "15") (name "Net-(Q9-D)") (class "Default")
      (node (ref "C57") (pin "2") (pinfunction "2_2") (pintype "passive"))
      (node (ref "Q9") (pin "1") (pinfunction "D_1") (pintype "passive"))
      (node (ref "R98") (pin "2") (pinfunction "2_2") (pintype "passive"))
    )
    (net (code "16") (name "Net-(R76-Pad1)") (class "Default")
      (node (ref "R76") (pin "1") (pinfunction "1_1") (pintype "passive"))
      (node (ref "R77") (pin "2") (pinfunction "2_2") (pintype "passive"))
    )
    (net (code "17") (name "Net-(R83-Pad1)") (class "Default")
      (node (ref "R83") (pin "1") (pinfunction "1_1") (pintype "passive"))
      (node (ref "R84") (pin "2") (pinfunction "2_2") (pintype "passive"))
    )
    (net (code "18") (name "Net-(R91-Pad1)") (class "Default")
      (node (ref "R91") (pin "1") (pinfunction "1_1") (pintype "passive"))
      (node (ref "R92") (pin "2") (pinfunction "2_2") (pintype "passive"))
    )
    (net (code "19") (name "Net-(U18-FB)") (class "Default")
      (node (ref "C32") (pin "1") (pinfunction "1_1") (pintype "passive"))
      (node (ref "R76") (pin "2") (pinfunction "2_2") (pintype "passive"))
      (node (ref "R80") (pin "1") (pinfunction "1_1") (pintype "passive"))
      (node (ref "U18") (pin "6") (pinfunction "FB_6") (pintype "power_in"))
    )
    (net (code "20") (name "Net-(U18-RON)") (class "Default")
      (node (ref "R75") (pin "1") (pinfunction "1_1") (pintype "passive"))
      (node (ref "U18") (pin "2") (pinfunction "RON_2") (pintype "power_in"))
    )
    (net (code "21") (name "Net-(U18-SS)") (class "Default")
      (node (ref "C33") (pin "1") (pinfunction "1_1") (pintype "passive"))
      (node (ref "U18") (pin "5") (pinfunction "SS_5") (pintype "power_in"))
    )
    (net (code "22") (name "Net-(U18-VIN)") (class "Default")
      (node (ref "C22") (pin "1") (pinfunction "1_1") (pintype "passive"))
      (node (ref "C23") (pin "1") (pinfunction "1_1") (pintype "passive"))
      (node (ref "C24") (pin "1") (pinfunction "1_1") (pintype "passive"))
      (node (ref "C25") (pin "1") (pinfunction "1_1") (pintype "passive"))
      (node (ref "FB4") (pin "2") (pinfunction "2_2") (pintype "passive"))
      (node (ref "R75") (pin "2") (pinfunction "2_2") (pintype "passive"))
      (node (ref "U18") (pin "1") (pinfunction "VIN_1") (pintype "power_in"))
    )
    (net (code "23") (name "Net-(U19-FB)") (class "Default")
      (node (ref "C43") (pin "1") (pinfunction "1_1") (pintype "passive"))
      (node (ref "R83") (pin "2") (pinfunction "2_2") (pintype "passive"))
      (node (ref "R86") (pin "1") (pinfunction "1_1") (pintype "passive"))
      (node (ref "U19") (pin "6") (pinfunction "FB_6") (pintype "power_in"))
    )
    (net (code "24") (name "Net-(U19-RON)") (class "Default")
      (node (ref "R82") (pin "1") (pinfunction "1_1") (pintype "passive"))
      (node (ref "U19") (pin "2") (pinfunction "RON_2") (pintype "power_in"))
    )
    (net (code "25") (name "Net-(U19-SS)") (class "Default")
      (node (ref "C44") (pin "1") (pinfunction "1_1") (pintype "passive"))
      (node (ref "U19") (pin "5") (pinfunction "SS_5") (pintype "power_in"))
    )
    (net (code "26") (name "Net-(U19-VIN)") (class "Default")
      (node (ref "C34") (pin "1") (pinfunction "1_1") (pintype "passive"))
      (node (ref "C35") (pin "1") (pinfunction "1_1") (pintype "passive"))
      (node (ref "C36") (pin "1") (pinfunction "1_1") (pintype "passive"))
      (node (ref "C37") (pin "1") (pinfunction "1_1") (pintype "passive"))
      (node (ref "FB5") (pin "2") (pinfunction "2_2") (pintype "passive"))
      (node (ref "R82") (pin "2") (pinfunction "2_2") (pintype "passive"))
      (node (ref "U19") (pin "1") (pinfunction "VIN_1") (pintype "power_in"))
    )
    (net (code "27") (name "Net-(U20-FB)") (class "Default")
      (node (ref "C55") (pin "1") (pinfunction "1_1") (pintype "passive"))
      (node (ref "R91") (pin "2") (pinfunction "2_2") (pintype "passive"))
      (node (ref "R94") (pin "1") (pinfunction "1_1") (pintype "passive"))
      (node (ref "U20") (pin "6") (pinfunction "FB_6") (pintype "power_in"))
    )
    (net (code "28") (name "Net-(U20-RON)") (class "Default")
      (node (ref "R90") (pin "1") (pinfunction "1_1") (pintype "passive"))
      (node (ref "U20") (pin "2") (pinfunction "RON_2") (pintype "power_in"))
    )
    (net (code "29") (name "Net-(U20-SS)") (class "Default")
      (node (ref "C56") (pin "1") (pinfunction "1_1") (pintype "passive"))
      (node (ref "U20") (pin "5") (pinfunction "SS_5") (pintype "power_in"))
    )
    (net (code "30") (name "Net-(U20-VIN)") (class "Default")
      (node (ref "C46") (pin "1") (pinfunction "1_1") (pintype "passive"))
      (node (ref "C47") (pin "1") (pinfunction "1_1") (pintype "passive"))
      (node (ref "C48") (pin "1") (pinfunction "1_1") (pintype "passive"))
      (node (ref "C49") (pin "1") (pinfunction "1_1") (pintype "passive"))
      (node (ref "FB6") (pin "2") (pinfunction "2_2") (pintype "passive"))
      (node (ref "R90") (pin "2") (pinfunction "2_2") (pintype "passive"))
      (node (ref "U20") (pin "1") (pinfunction "VIN_1") (pintype "power_in"))
    )
    (net (code "31") (name "VDD_3V3") (class "Default")
      (node (ref "C26") (pin "1") (pinfunction "1_1") (pintype "passive"))
      (node (ref "C27") (pin "1") (pinfunction "1_1") (pintype "passive"))
      (node (ref "C28") (pin "1") (pinfunction "1_1") (pintype "passive"))
      (node (ref "C29") (pin "1") (pinfunction "1_1") (pintype "passive"))
      (node (ref "C31") (pin "2") (pinfunction "2_2") (pintype "passive"))
      (node (ref "C32") (pin "2") (pinfunction "2_2") (pintype "passive"))
      (node (ref "R77") (pin "1") (pinfunction "1_1") (pintype "passive"))
      (node (ref "U18") (pin "7") (pinfunction "VOUT_7") (pintype "power_in"))
    )
    (net (code "32") (name "VDD_3V3B") (class "Default")
      (node (ref "Q7") (pin "2") (pinfunction "G_2") (pintype "passive"))
      (node (ref "Q9") (pin "2") (pinfunction "G_2") (pintype "passive"))
      (node (ref "R93") (pin "1") (pinfunction "1_1") (pintype "passive"))
      (node (ref "R99") (pin "1") (pinfunction "1_1") (pintype "passive"))
    )
    (net (code "33") (name "VDD_5V0") (class "Default")
      (node (ref "C38") (pin "1") (pinfunction "1_1") (pintype "passive"))
      (node (ref "C39") (pin "1") (pinfunction "1_1") (pintype "passive"))
      (node (ref "C40") (pin "1") (pinfunction "1_1") (pintype "passive"))
      (node (ref "C41") (pin "1") (pinfunction "1_1") (pintype "passive"))
      (node (ref "C42") (pin "2") (pinfunction "2_2") (pintype "passive"))
      (node (ref "C43") (pin "2") (pinfunction "2_2") (pintype "passive"))
      (node (ref "R84") (pin "1") (pinfunction "1_1") (pintype "passive"))
      (node (ref "U19") (pin "7") (pinfunction "VOUT_7") (pintype "power_in"))
    )
    (net (code "34") (name "VDD_12V0") (class "Default")
      (node (ref "C50") (pin "1") (pinfunction "1_1") (pintype "passive"))
      (node (ref "C51") (pin "1") (pinfunction "1_1") (pintype "passive"))
      (node (ref "C52") (pin "1") (pinfunction "1_1") (pintype "passive"))
      (node (ref "C53") (pin "1") (pinfunction "1_1") (pintype "passive"))
      (node (ref "C54") (pin "2") (pinfunction "2_2") (pintype "passive"))
      (node (ref "C55") (pin "2") (pinfunction "2_2") (pintype "passive"))
      (node (ref "R92") (pin "1") (pinfunction "1_1") (pintype "passive"))
      (node (ref "U20") (pin "7") (pinfunction "VOUT_7") (pintype "power_in"))
    )
  )
)
